# ac-adapter1.net
KiCad netlist of a schematic drawn in EAGLE
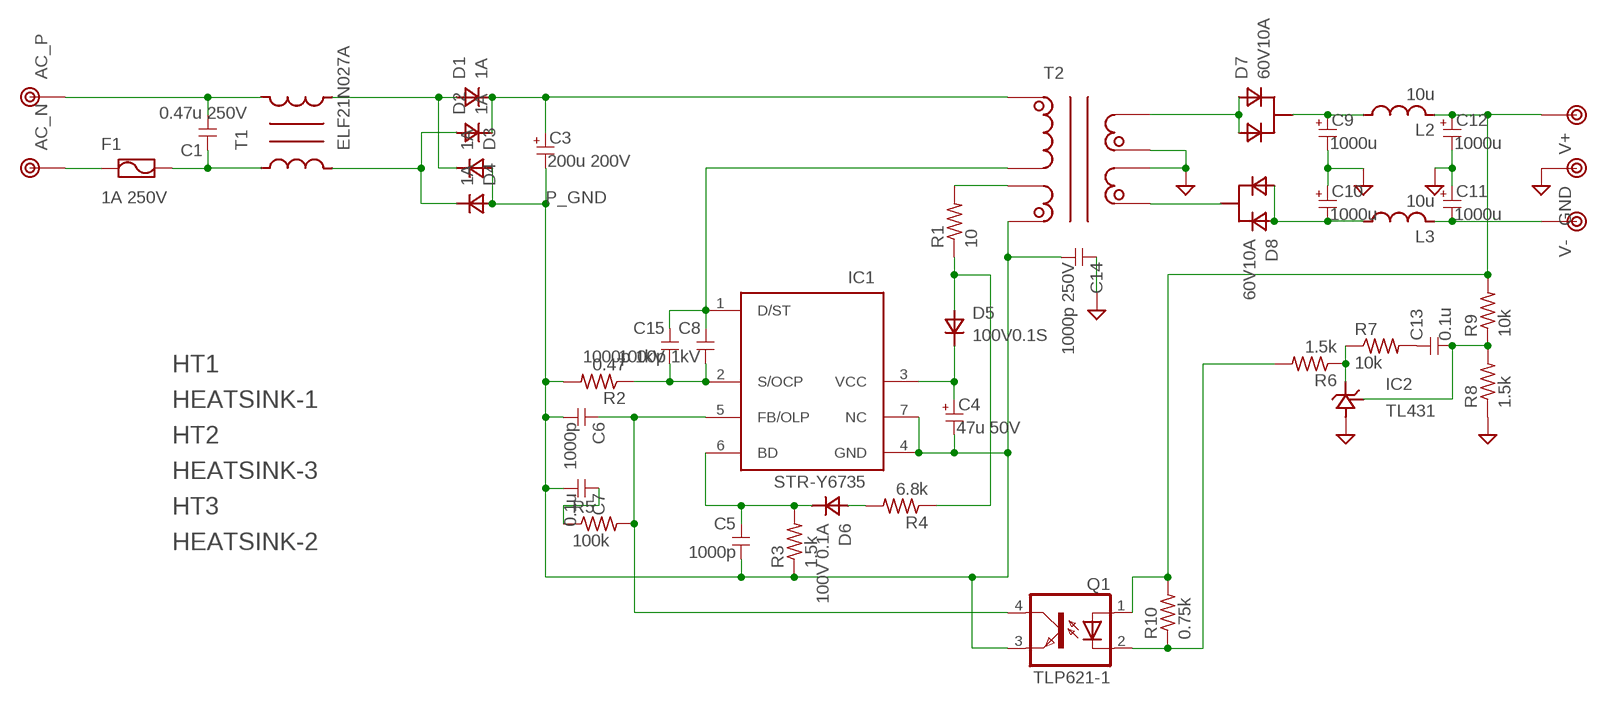
[diagram p0: schematic, sheet 1]

(export (version "E")
  (design (tool "Eeschema 10.0.6"))
  (components
    (comp (ref "C1")
      (value "0.47u 250V")
      (footprint "eagle-import:C050-030X075")
      (libsource (lib "eagle-import") (part "C-5"))
    )
    (comp (ref "C3")
      (value "200u 200V")
      (footprint "eagle-import:E5-13")
      (libsource (lib "eagle-import") (part "CPOLE5-13"))
    )
    (comp (ref "C4")
      (value "47u 50V")
      (footprint "eagle-import:E2.5-6.5")
      (libsource (lib "eagle-import") (part "CPOLE2.5-6.5"))
    )
    (comp (ref "C5")
      (value "1000p")
      (footprint "eagle-import:1608")
      (libsource (lib "eagle-import") (part "C-1608"))
    )
    (comp (ref "C6")
      (value "1000p")
      (footprint "eagle-import:1608")
      (libsource (lib "eagle-import") (part "C-1608"))
    )
    (comp (ref "C7")
      (value "0.1u")
      (footprint "eagle-import:1608")
      (libsource (lib "eagle-import") (part "C-1608"))
    )
    (comp (ref "C8")
      (value "1000p 1kV")
      (footprint "eagle-import:C050-030X075")
      (libsource (lib "eagle-import") (part "C-5"))
    )
    (comp (ref "C9")
      (value "1000u")
      (footprint "eagle-import:E2,5-8")
      (libsource (lib "eagle-import") (part "CPOLE2.5-8"))
    )
    (comp (ref "C10")
      (value "1000u")
      (footprint "eagle-import:E2,5-8")
      (libsource (lib "eagle-import") (part "CPOLE2.5-8"))
    )
    (comp (ref "C11")
      (value "1000u")
      (footprint "eagle-import:E2,5-8")
      (libsource (lib "eagle-import") (part "CPOLE2.5-8"))
    )
    (comp (ref "C12")
      (value "1000u")
      (footprint "eagle-import:E2,5-8")
      (libsource (lib "eagle-import") (part "CPOLE2.5-8"))
    )
    (comp (ref "C13")
      (value "0.1u")
      (footprint "eagle-import:1608")
      (libsource (lib "eagle-import") (part "C-1608"))
    )
    (comp (ref "C14")
      (value "1000p 250V")
      (footprint "eagle-import:C050-030X075")
      (libsource (lib "eagle-import") (part "C-5"))
    )
    (comp (ref "C15")
      (value "1000p 1kV")
      (footprint "eagle-import:C050-030X075")
      (libsource (lib "eagle-import") (part "C-5"))
    )
    (comp (ref "D1")
      (value "1A")
      (footprint "eagle-import:D0204_7")
      (libsource (lib "eagle-import") (part "DIODE-7"))
    )
    (comp (ref "D2")
      (value "1A")
      (footprint "eagle-import:D0204_7")
      (libsource (lib "eagle-import") (part "DIODE-7"))
    )
    (comp (ref "D3")
      (value "1A")
      (footprint "eagle-import:D0204_7")
      (libsource (lib "eagle-import") (part "DIODE-7"))
    )
    (comp (ref "D4")
      (value "1A")
      (footprint "eagle-import:D0204_7")
      (libsource (lib "eagle-import") (part "DIODE-7"))
    )
    (comp (ref "D5")
      (value "100V0.1S")
      (footprint "eagle-import:D0207_2V")
      (libsource (lib "eagle-import") (part "DIODE-2"))
    )
    (comp (ref "D6")
      (value "100V 0.1A")
      (footprint "eagle-import:D0207_2V")
      (libsource (lib "eagle-import") (part "DIODE-2"))
    )
    (comp (ref "D7")
      (value "60V10A")
      (footprint "eagle-import:TO-220")
      (libsource (lib "eagle-import") (part "DIODE2"))
    )
    (comp (ref "D8")
      (value "60V10A")
      (footprint "eagle-import:TO-220")
      (libsource (lib "eagle-import") (part "DIODE2"))
    )
    (comp (ref "F1")
      (value "1A 250V")
      (footprint "eagle-import:FUSE_20MM")
      (libsource (lib "eagle-import") (part "FUSE-20MM"))
    )
    (comp (ref "HT1")
      (value "HEATSINK-1")
      (footprint "eagle-import:HEATSINK1")
      (libsource (lib "eagle-import") (part "HEATSINK-1"))
    )
    (comp (ref "HT2")
      (value "HEATSINK-3")
      (footprint "eagle-import:HEATSINK3")
      (libsource (lib "eagle-import") (part "HEATSINK-3"))
    )
    (comp (ref "HT3")
      (value "HEATSINK-2")
      (footprint "eagle-import:HEATSINK2")
      (libsource (lib "eagle-import") (part "HEATSINK-2"))
    )
    (comp (ref "IC1")
      (value "STR-Y6735")
      (footprint "eagle-import:TO220F-7L-UNIVERSAL")
      (libsource (lib "eagle-import") (part "STR-Y6700-UNIVERSAL"))
    )
    (comp (ref "IC2")
      (value "TL431")
      (footprint "eagle-import:TO-92")
      (libsource (lib "eagle-import") (part "TL431"))
    )
    (comp (ref "L2")
      (value "10u")
      (footprint "eagle-import:L5-7,5")
      (libsource (lib "eagle-import") (part "L-5"))
    )
    (comp (ref "L3")
      (value "10u")
      (footprint "eagle-import:L5-7,5")
      (libsource (lib "eagle-import") (part "L-5"))
    )
    (comp (ref "Q1")
      (value "TLP621-1")
      (footprint "eagle-import:DIL04")
      (libsource (lib "eagle-import") (part "TLP621-1"))
    )
    (comp (ref "R1")
      (value "10")
      (footprint "eagle-import:0207_10")
      (libsource (lib "eagle-import") (part "R-10"))
    )
    (comp (ref "R2")
      (value "0.47")
      (footprint "eagle-import:0207_10")
      (libsource (lib "eagle-import") (part "R-10"))
    )
    (comp (ref "R3")
      (value "1.5k")
      (footprint "eagle-import:1608")
      (libsource (lib "eagle-import") (part "R-1608"))
    )
    (comp (ref "R4")
      (value "6.8k")
      (footprint "eagle-import:0207_2V")
      (libsource (lib "eagle-import") (part "R-2.5"))
    )
    (comp (ref "R5")
      (value "100k")
      (footprint "eagle-import:1608")
      (libsource (lib "eagle-import") (part "R-1608"))
    )
    (comp (ref "R6")
      (value "1.5k")
      (footprint "eagle-import:1608")
      (libsource (lib "eagle-import") (part "R-1608"))
    )
    (comp (ref "R7")
      (value "10k")
      (footprint "eagle-import:1608")
      (libsource (lib "eagle-import") (part "R-1608"))
    )
    (comp (ref "R8")
      (value "1.5k")
      (footprint "eagle-import:1608")
      (libsource (lib "eagle-import") (part "R-1608"))
    )
    (comp (ref "R9")
      (value "10k")
      (footprint "eagle-import:1608")
      (libsource (lib "eagle-import") (part "R-1608"))
    )
    (comp (ref "R10")
      (value "0.75k")
      (footprint "eagle-import:1608")
      (libsource (lib "eagle-import") (part "R-1608"))
    )
    (comp (ref "T1")
      (value "ELF21N027A")
      (footprint "eagle-import:ELF21N027A")
      (libsource (lib "eagle-import") (part "ELF21N027A"))
    )
    (comp (ref "T2")
      (value "TRANSFORMAER_FLYBACK-PQ3535")
      (footprint "eagle-import:BPQ35_35-1112CPFR")
      (libsource (lib "eagle-import") (part "TRANSFORMAER_FLYBACK-PQ3535"))
    )
    (comp (ref "TP1")
      (value "AC_P")
      (footprint "eagle-import:TESTPIN")
      (libsource (lib "eagle-import") (part "TESTPIN"))
    )
    (comp (ref "TP2")
      (value "AC_N")
      (footprint "eagle-import:TESTPIN")
      (libsource (lib "eagle-import") (part "TESTPIN"))
    )
    (comp (ref "TP3")
      (value "V+")
      (footprint "eagle-import:TESTPIN")
      (libsource (lib "eagle-import") (part "TESTPIN"))
    )
    (comp (ref "TP4")
      (value "V-")
      (footprint "eagle-import:TESTPIN")
      (libsource (lib "eagle-import") (part "TESTPIN"))
    )
    (comp (ref "TP5")
      (value "GND")
      (footprint "eagle-import:TESTPIN")
      (libsource (lib "eagle-import") (part "TESTPIN"))
    )
  )
  (nets
    (net (code "1") (name "/P_GND") (class "Default")
      (node (ref "C14") (pin "2") (pinfunction "2_2") (pintype "passive"))
      (node (ref "C3") (pin "-") (pinfunction "2_-") (pintype "passive"))
      (node (ref "C4") (pin "-") (pinfunction "2_-") (pintype "passive"))
      (node (ref "C5") (pin "2") (pinfunction "2_2") (pintype "passive"))
      (node (ref "C6") (pin "2") (pinfunction "2_2") (pintype "passive"))
      (node (ref "C7") (pin "2") (pinfunction "2_2") (pintype "passive"))
      (node (ref "D3") (pin "1") (pinfunction "A_1") (pintype "passive"))
      (node (ref "D4") (pin "1") (pinfunction "A_1") (pintype "passive"))
      (node (ref "IC1") (pin "4") (pinfunction "GND_4") (pintype "power_in"))
      (node (ref "IC1") (pin "7") (pinfunction "NC_7") (pintype "input"))
      (node (ref "Q1") (pin "3") (pinfunction "EMIT_3") (pintype "passive"))
      (node (ref "R2") (pin "2") (pinfunction "2_2") (pintype "passive"))
      (node (ref "R3") (pin "1") (pinfunction "1_1") (pintype "passive"))
      (node (ref "T2") (pin "4") (pinfunction "L2_P_4") (pintype "passive"))
    )
    (net (code "2") (name "GND") (class "Default")
      (node (ref "C10") (pin "+") (pinfunction "1_+") (pintype "passive"))
      (node (ref "C11") (pin "+") (pinfunction "1_+") (pintype "passive"))
      (node (ref "C12") (pin "-") (pinfunction "2_-") (pintype "passive"))
      (node (ref "C14") (pin "1") (pinfunction "1_1") (pintype "passive"))
      (node (ref "C9") (pin "-") (pinfunction "2_-") (pintype "passive"))
      (node (ref "IC2") (pin "2") (pinfunction "GND_2") (pintype "bidirectional"))
      (node (ref "R8") (pin "1") (pinfunction "1_1") (pintype "passive"))
      (node (ref "T2") (pin "10") (pinfunction "L4_N_10") (pintype "passive"))
      (node (ref "T2") (pin "9") (pinfunction "L3_P_9") (pintype "passive"))
      (node (ref "TP5") (pin "1") (pinfunction "1_1") (pintype "passive"))
    )
    (net (code "3") (name "Net-(C1-Pad1)") (class "Default")
      (node (ref "C1") (pin "1") (pinfunction "1_1") (pintype "passive"))
      (node (ref "F1") (pin "2-1") (pinfunction "P$2_2-1") (pintype "passive"))
      (node (ref "F1") (pin "2-2") (pinfunction "P$2_2-2") (pintype "passive"))
      (node (ref "T1") (pin "1") (pinfunction "1_1") (pintype "passive"))
    )
    (net (code "4") (name "Net-(C1-Pad2)") (class "Default")
      (node (ref "C1") (pin "2") (pinfunction "2_2") (pintype "passive"))
      (node (ref "T1") (pin "4") (pinfunction "4_4") (pintype "passive"))
      (node (ref "TP1") (pin "1") (pinfunction "1_1") (pintype "passive"))
    )
    (net (code "5") (name "Net-(C3-1)") (class "Default")
      (node (ref "C3") (pin "+") (pinfunction "1_+") (pintype "passive"))
      (node (ref "D1") (pin "2") (pinfunction "K_2") (pintype "passive"))
      (node (ref "D2") (pin "2") (pinfunction "K_2") (pintype "passive"))
      (node (ref "T2") (pin "1") (pinfunction "L1_P_1") (pintype "passive"))
    )
    (net (code "6") (name "Net-(C4-1)") (class "Default")
      (node (ref "C4") (pin "+") (pinfunction "1_+") (pintype "passive"))
      (node (ref "D5") (pin "2") (pinfunction "K_2") (pintype "passive"))
      (node (ref "IC1") (pin "3") (pinfunction "VCC_3") (pintype "power_in"))
    )
    (net (code "7") (name "Net-(C7-Pad1)") (class "Default")
      (node (ref "C7") (pin "1") (pinfunction "1_1") (pintype "passive"))
      (node (ref "R5") (pin "1") (pinfunction "1_1") (pintype "passive"))
    )
    (net (code "8") (name "Net-(C9-1)") (class "Default")
      (node (ref "C9") (pin "+") (pinfunction "1_+") (pintype "passive"))
      (node (ref "D7") (pin "2") (pinfunction "K_2") (pintype "passive"))
      (node (ref "L2") (pin "P$1") (pinfunction "1_P$1") (pintype "passive"))
    )
    (net (code "9") (name "Net-(C10-2)") (class "Default")
      (node (ref "C10") (pin "-") (pinfunction "2_-") (pintype "passive"))
      (node (ref "D8") (pin "1") (pinfunction "A1_1") (pintype "passive"))
      (node (ref "D8") (pin "3") (pinfunction "A2_3") (pintype "passive"))
      (node (ref "L3") (pin "P$1") (pinfunction "1_P$1") (pintype "passive"))
    )
    (net (code "10") (name "Net-(C11-2)") (class "Default")
      (node (ref "C11") (pin "-") (pinfunction "2_-") (pintype "passive"))
      (node (ref "L3") (pin "P$2") (pinfunction "2_P$2") (pintype "passive"))
      (node (ref "TP4") (pin "1") (pinfunction "1_1") (pintype "passive"))
    )
    (net (code "11") (name "Net-(C12-1)") (class "Default")
      (node (ref "C12") (pin "+") (pinfunction "1_+") (pintype "passive"))
      (node (ref "L2") (pin "P$2") (pinfunction "2_P$2") (pintype "passive"))
      (node (ref "Q1") (pin "1") (pinfunction "A_1") (pintype "passive"))
      (node (ref "R10") (pin "2") (pinfunction "2_2") (pintype "passive"))
      (node (ref "R9") (pin "2") (pinfunction "2_2") (pintype "passive"))
      (node (ref "TP3") (pin "1") (pinfunction "1_1") (pintype "passive"))
    )
    (net (code "12") (name "Net-(C13-Pad1)") (class "Default")
      (node (ref "C13") (pin "1") (pinfunction "1_1") (pintype "passive"))
      (node (ref "R7") (pin "2") (pinfunction "2_2") (pintype "passive"))
    )
    (net (code "13") (name "Net-(D1-A)") (class "Default")
      (node (ref "D1") (pin "1") (pinfunction "A_1") (pintype "passive"))
      (node (ref "D3") (pin "2") (pinfunction "K_2") (pintype "passive"))
      (node (ref "T1") (pin "3") (pinfunction "3_3") (pintype "passive"))
    )
    (net (code "14") (name "Net-(D2-A)") (class "Default")
      (node (ref "D2") (pin "1") (pinfunction "A_1") (pintype "passive"))
      (node (ref "D4") (pin "2") (pinfunction "K_2") (pintype "passive"))
      (node (ref "T1") (pin "2") (pinfunction "2_2") (pintype "passive"))
    )
    (net (code "15") (name "Net-(D5-A)") (class "Default")
      (node (ref "D5") (pin "1") (pinfunction "A_1") (pintype "passive"))
      (node (ref "R1") (pin "1") (pinfunction "1_1") (pintype "passive"))
      (node (ref "R4") (pin "1") (pinfunction "1_1") (pintype "passive"))
    )
    (net (code "16") (name "Net-(D6-A)") (class "Default")
      (node (ref "D6") (pin "1") (pinfunction "A_1") (pintype "passive"))
      (node (ref "R4") (pin "2") (pinfunction "2_2") (pintype "passive"))
    )
    (net (code "17") (name "Net-(D6-K)") (class "Default")
      (node (ref "C5") (pin "1") (pinfunction "1_1") (pintype "passive"))
      (node (ref "D6") (pin "2") (pinfunction "K_2") (pintype "passive"))
      (node (ref "IC1") (pin "6") (pinfunction "BD_6") (pintype "input"))
      (node (ref "R3") (pin "2") (pinfunction "2_2") (pintype "passive"))
    )
    (net (code "18") (name "Net-(D7-A1)") (class "Default")
      (node (ref "D7") (pin "1") (pinfunction "A1_1") (pintype "passive"))
      (node (ref "D7") (pin "3") (pinfunction "A2_3") (pintype "passive"))
      (node (ref "T2") (pin "8") (pinfunction "L3_N_8") (pintype "passive"))
    )
    (net (code "19") (name "Net-(D8-K)") (class "Default")
      (node (ref "D8") (pin "2") (pinfunction "K_2") (pintype "passive"))
      (node (ref "T2") (pin "11") (pinfunction "L4_P_11") (pintype "passive"))
    )
    (net (code "20") (name "Net-(F1-P$1-Pad1-1)") (class "Default")
      (node (ref "F1") (pin "1-1") (pinfunction "P$1_1-1") (pintype "passive"))
      (node (ref "F1") (pin "1-2") (pinfunction "P$1_1-2") (pintype "passive"))
      (node (ref "TP2") (pin "1") (pinfunction "1_1") (pintype "passive"))
    )
    (net (code "21") (name "Net-(IC1-D{slash}ST)") (class "Default")
      (node (ref "C15") (pin "1") (pinfunction "1_1") (pintype "passive"))
      (node (ref "C8") (pin "1") (pinfunction "1_1") (pintype "passive"))
      (node (ref "IC1") (pin "1") (pinfunction "D/ST_1") (pintype "output"))
      (node (ref "T2") (pin "3") (pinfunction "L1_N_3") (pintype "passive"))
    )
    (net (code "22") (name "Net-(IC1-FB{slash}OLP)") (class "Default")
      (node (ref "C6") (pin "1") (pinfunction "1_1") (pintype "passive"))
      (node (ref "IC1") (pin "5") (pinfunction "FB/OLP_5") (pintype "input"))
      (node (ref "Q1") (pin "4") (pinfunction "COL_4") (pintype "passive"))
      (node (ref "R5") (pin "2") (pinfunction "2_2") (pintype "passive"))
    )
    (net (code "23") (name "Net-(IC1-S{slash}OCP)") (class "Default")
      (node (ref "C15") (pin "2") (pinfunction "2_2") (pintype "passive"))
      (node (ref "C8") (pin "2") (pinfunction "2_2") (pintype "passive"))
      (node (ref "IC1") (pin "2") (pinfunction "S/OCP_2") (pintype "input"))
      (node (ref "R2") (pin "1") (pinfunction "1_1") (pintype "passive"))
    )
    (net (code "24") (name "Net-(IC2-OUT)") (class "Default")
      (node (ref "IC2") (pin "3") (pinfunction "OUT_3") (pintype "bidirectional"))
      (node (ref "R6") (pin "1") (pinfunction "1_1") (pintype "passive"))
      (node (ref "R7") (pin "1") (pinfunction "1_1") (pintype "passive"))
    )
    (net (code "25") (name "Net-(IC2-REF)") (class "Default")
      (node (ref "C13") (pin "2") (pinfunction "2_2") (pintype "passive"))
      (node (ref "IC2") (pin "1") (pinfunction "REF_1") (pintype "input"))
      (node (ref "R8") (pin "2") (pinfunction "2_2") (pintype "passive"))
      (node (ref "R9") (pin "1") (pinfunction "1_1") (pintype "passive"))
    )
    (net (code "26") (name "Net-(Q1-C)") (class "Default")
      (node (ref "Q1") (pin "2") (pinfunction "C_2") (pintype "passive"))
      (node (ref "R10") (pin "1") (pinfunction "1_1") (pintype "passive"))
      (node (ref "R6") (pin "2") (pinfunction "2_2") (pintype "passive"))
    )
    (net (code "27") (name "Net-(T2-L2_N)") (class "Default")
      (node (ref "R1") (pin "2") (pinfunction "2_2") (pintype "passive"))
      (node (ref "T2") (pin "5") (pinfunction "L2_N_5") (pintype "passive"))
    )
  )
)
